# POWER_IN_12V2A.net
KiCad netlist of a schematic drawn in Altium Designer
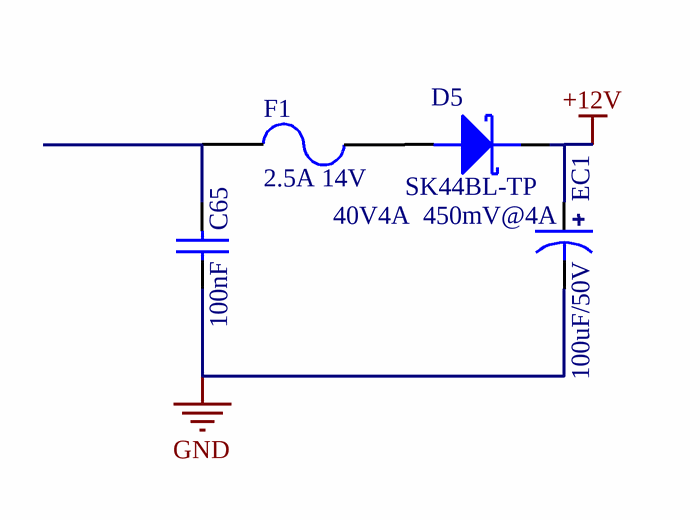
[diagram p0: POWER IN 12V2A.SchDoc]

(export (version "E")
  (design (tool "Eeschema 10.0.6"))
  (components
    (comp (ref "C65")
      (value "100nF")
      (footprint "C_0603")
      (description "贴片电容")
      (libsource (lib "IntLib-Passive") (part "Cap_Chip"))
    )
    (comp (ref "D5")
      (value "40V4A  450mV@4A")
      (footprint "SMB_DO214AA")
      (description "肖特基二极管")
      (fields (field (name "MANUFACTURER_PART_NUMBER") "SK44BL-TP"))
      (libsource (lib "IntLib-Active") (part "Diode_Schottky"))
    )
    (comp (ref "EC1")
      (value "100uF/50V")
      (footprint "SMD-D6.3XL7.7")
      (description "贴片电解电容")
      (fields (field (name "MANUFACTURER_PART_NUMBER") "RX100UF50V90RV0105"))
      (libsource (lib "IntLib-Passive") (part "Cap_E_SMD"))
    )
    (comp (ref "F1")
      (value "2.5A 14V")
      (footprint "IntLib-Passive:Fuse_1812")
      (description "自恢复贴片保险丝")
      (fields (field (name "MANUFACTURER_PART_NUMBER") "C381482"))
      (libsource (lib "Passive-Fuse") (part "FUSE_PTC"))
    )
  )
  (nets
    (net (code "1") (name "+12V") (class "Default")
      (node (ref "D5") (pin "K") (pinfunction "K_K") (pintype "passive"))
      (node (ref "EC1") (pin "1") (pinfunction "1_1") (pintype "passive"))
    )
    (net (code "2") (name "GND") (class "Default")
      (node (ref "C65") (pin "2") (pinfunction "2_2") (pintype "passive"))
      (node (ref "EC1") (pin "2") (pinfunction "2_2") (pintype "passive"))
    )
    (net (code "3") (name "Net-(C65-Pad1)") (class "Default")
      (node (ref "C65") (pin "1") (pinfunction "1_1") (pintype "passive"))
      (node (ref "F1") (pin "1") (pinfunction "1_1") (pintype "passive"))
    )
    (net (code "4") (name "Net-(D5-PadA)") (class "Default")
      (node (ref "D5") (pin "A") (pinfunction "A_A") (pintype "passive"))
      (node (ref "F1") (pin "2") (pinfunction "2_2") (pintype "passive"))
    )
  )
)
